# ampli.net
KiCad netlist of a schematic drawn in EAGLE
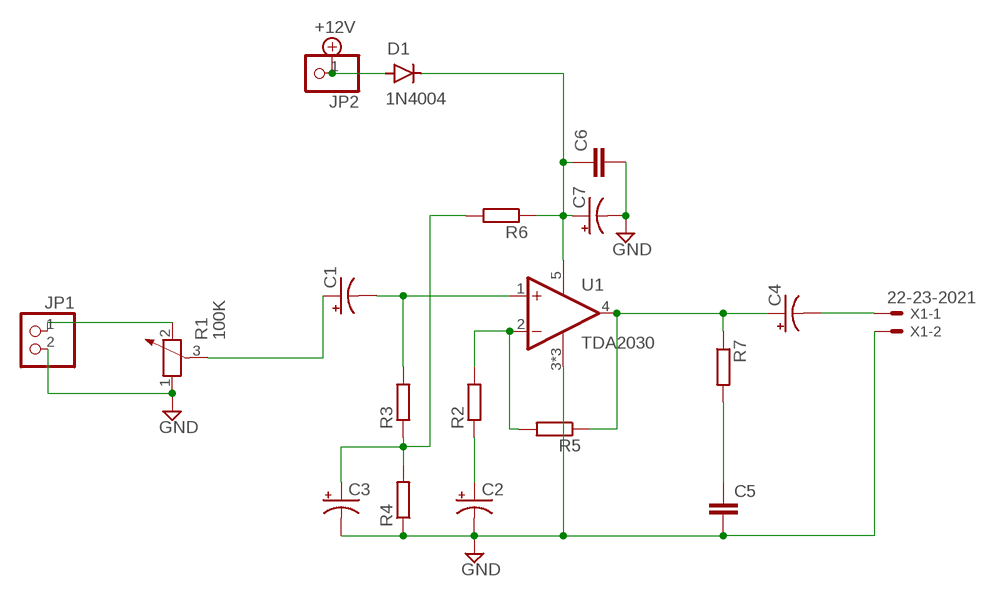
[diagram p0: schematic, sheet 1]

(export (version "E")
  (design (tool "Eeschema 10.0.6"))
  (components
    (comp (ref "C1")
      (value "CPOL-USB45181A")
      (footprint "eagle-import:B45181A")
      (libsource (lib "eagle-import") (part "CPOL-USB45181A"))
    )
    (comp (ref "C2")
      (value "CPOL-USB45181A")
      (footprint "eagle-import:B45181A")
      (libsource (lib "eagle-import") (part "CPOL-USB45181A"))
    )
    (comp (ref "C3")
      (value "CPOL-USB45181A")
      (footprint "eagle-import:B45181A")
      (libsource (lib "eagle-import") (part "CPOL-USB45181A"))
    )
    (comp (ref "C4")
      (value "CPOL-USB45181B")
      (footprint "eagle-import:B45181B")
      (libsource (lib "eagle-import") (part "CPOL-USB45181B"))
    )
    (comp (ref "C5")
      (value "C-EU025-024X044")
      (footprint "eagle-import:C025-024X044")
      (libsource (lib "eagle-import") (part "C-EU025-024X044"))
    )
    (comp (ref "C6")
      (value "C-EU025-024X044")
      (footprint "eagle-import:C025-024X044")
      (libsource (lib "eagle-import") (part "C-EU025-024X044"))
    )
    (comp (ref "C7")
      (value "CPOL-USB45181B")
      (footprint "eagle-import:B45181B")
      (libsource (lib "eagle-import") (part "CPOL-USB45181B"))
    )
    (comp (ref "D1")
      (value "1N4004")
      (footprint "eagle-import:DO-41")
      (fields
        (field (name "DIGIKEY_PART_NUMBER") "1N4004MSCT-ND")
        (field (name "MANUFACTURER") "Micro Commercial Co")
        (field (name "CREATED_BY") "PCBLayout.com")
      )
      (libsource (lib "eagle-import") (part "1N4004"))
    )
    (comp (ref "JP1")
      (value "PINHD-1X2")
      (footprint "eagle-import:1X02")
      (libsource (lib "eagle-import") (part "PINHD-1X2"))
    )
    (comp (ref "JP2")
      (value "PINHD-1X1")
      (footprint "eagle-import:1X01")
      (libsource (lib "eagle-import") (part "PINHD-1X1"))
    )
    (comp (ref "R1")
      (value "100K")
      (footprint "eagle-import:PT-10")
      (libsource (lib "eagle-import") (part "POTENTIOMETER_PT-10"))
    )
    (comp (ref "R2")
      (value "R-EU_0204/5")
      (footprint "eagle-import:0204_5")
      (libsource (lib "eagle-import") (part "R-EU_0204/5"))
    )
    (comp (ref "R3")
      (value "R-EU_0204/5")
      (footprint "eagle-import:0204_5")
      (libsource (lib "eagle-import") (part "R-EU_0204/5"))
    )
    (comp (ref "R4")
      (value "R-EU_0204/5")
      (footprint "eagle-import:0204_5")
      (libsource (lib "eagle-import") (part "R-EU_0204/5"))
    )
    (comp (ref "R5")
      (value "R-EU_0204/5")
      (footprint "eagle-import:0204_5")
      (libsource (lib "eagle-import") (part "R-EU_0204/5"))
    )
    (comp (ref "R6")
      (value "R-EU_0204/5")
      (footprint "eagle-import:0204_5")
      (libsource (lib "eagle-import") (part "R-EU_0204/5"))
    )
    (comp (ref "R7")
      (value "R-EU_0204/5")
      (footprint "eagle-import:0204_5")
      (libsource (lib "eagle-import") (part "R-EU_0204/5"))
    )
    (comp (ref "U1")
      (value "TDA2030")
      (footprint "eagle-import:TO170P1580X1040X480-5")
      (fields (field (name "MF") "STMicroelectronics"))
      (libsource (lib "eagle-import") (part "TDA2030"))
    )
    (comp (ref "X1")
      (value "22-23-2021")
      (footprint "eagle-import:22-23-2021")
      (fields (field (name "MF") "MOLEX"))
      (libsource (lib "eagle-import") (part "22-23-2021"))
    )
  )
  (nets
    (net (code "1") (name "+12V") (class "Default")
      (node (ref "D1") (pin "A") (pinfunction "A_A") (pintype "passive"))
      (node (ref "JP2") (pin "1") (pinfunction "1_1") (pintype "passive"))
    )
    (net (code "2") (name "GND") (class "Default")
      (node (ref "C2") (pin "-") (pinfunction "-_-") (pintype "passive"))
      (node (ref "C3") (pin "-") (pinfunction "-_-") (pintype "passive"))
      (node (ref "C5") (pin "2") (pinfunction "2_2") (pintype "passive"))
      (node (ref "C6") (pin "2") (pinfunction "2_2") (pintype "passive"))
      (node (ref "C7") (pin "-") (pinfunction "-_-") (pintype "passive"))
      (node (ref "JP1") (pin "2") (pinfunction "2_2") (pintype "passive"))
      (node (ref "R1") (pin "1") (pinfunction "1_1") (pintype "passive"))
      (node (ref "R4") (pin "1") (pinfunction "1_1") (pintype "passive"))
      (node (ref "U1") (pin "3") (pinfunction "-VS_3") (pintype "power_in"))
      (node (ref "U1") (pin "6") (pinfunction "-VS_6") (pintype "power_in"))
      (node (ref "U1") (pin "6.1") (pinfunction "-VS_6.1") (pintype "power_in"))
      (node (ref "X1") (pin "2") (pinfunction "S_2") (pintype "passive"))
    )
    (net (code "3") (name "Net-(C1-Pad+)") (class "Default")
      (node (ref "C1") (pin "+") (pinfunction "+_+") (pintype "passive"))
      (node (ref "R1") (pin "3") (pinfunction "3_3") (pintype "passive"))
    )
    (net (code "4") (name "Net-(C2-Pad+)") (class "Default")
      (node (ref "C2") (pin "+") (pinfunction "+_+") (pintype "passive"))
      (node (ref "R2") (pin "1") (pinfunction "1_1") (pintype "passive"))
    )
    (net (code "5") (name "Net-(C3-Pad+)") (class "Default")
      (node (ref "C3") (pin "+") (pinfunction "+_+") (pintype "passive"))
      (node (ref "R3") (pin "1") (pinfunction "1_1") (pintype "passive"))
      (node (ref "R4") (pin "2") (pinfunction "2_2") (pintype "passive"))
      (node (ref "R6") (pin "2") (pinfunction "2_2") (pintype "passive"))
    )
    (net (code "6") (name "Net-(C5-Pad1)") (class "Default")
      (node (ref "C5") (pin "1") (pinfunction "1_1") (pintype "passive"))
      (node (ref "R7") (pin "2") (pinfunction "2_2") (pintype "passive"))
    )
    (net (code "7") (name "Net-(JP1-Pad1)") (class "Default")
      (node (ref "JP1") (pin "1") (pinfunction "1_1") (pintype "passive"))
      (node (ref "R1") (pin "2") (pinfunction "2_2") (pintype "passive"))
    )
    (net (code "8") (name "Net-(U1-+VS)") (class "Default")
      (node (ref "C6") (pin "1") (pinfunction "1_1") (pintype "passive"))
      (node (ref "C7") (pin "+") (pinfunction "+_+") (pintype "passive"))
      (node (ref "D1") (pin "C") (pinfunction "C_C") (pintype "passive"))
      (node (ref "R6") (pin "1") (pinfunction "1_1") (pintype "passive"))
      (node (ref "U1") (pin "5") (pinfunction "+VS_5") (pintype "power_in"))
    )
    (net (code "9") (name "Net-(U1-INV_INPUT)") (class "Default")
      (node (ref "R2") (pin "2") (pinfunction "2_2") (pintype "passive"))
      (node (ref "R5") (pin "2") (pinfunction "2_2") (pintype "passive"))
      (node (ref "U1") (pin "2") (pinfunction "INV_INPUT_2") (pintype "input"))
    )
    (net (code "10") (name "Net-(U1-NON_INV_INPUT)") (class "Default")
      (node (ref "C1") (pin "-") (pinfunction "-_-") (pintype "passive"))
      (node (ref "R3") (pin "2") (pinfunction "2_2") (pintype "passive"))
      (node (ref "U1") (pin "1") (pinfunction "NON_INV_INPUT_1") (pintype "input"))
    )
    (net (code "11") (name "Net-(U1-OUTPUT)") (class "Default")
      (node (ref "C4") (pin "+") (pinfunction "+_+") (pintype "passive"))
      (node (ref "R5") (pin "1") (pinfunction "1_1") (pintype "passive"))
      (node (ref "R7") (pin "1") (pinfunction "1_1") (pintype "passive"))
      (node (ref "U1") (pin "4") (pinfunction "OUTPUT_4") (pintype "output"))
    )
    (net (code "12") (name "Net-(X1A-S)") (class "Default")
      (node (ref "C4") (pin "-") (pinfunction "-_-") (pintype "passive"))
      (node (ref "X1") (pin "1") (pinfunction "S_1") (pintype "passive"))
    )
  )
)
